# CoreBase-V2_0.net
KiCad netlist of a schematic drawn in Altium Designer
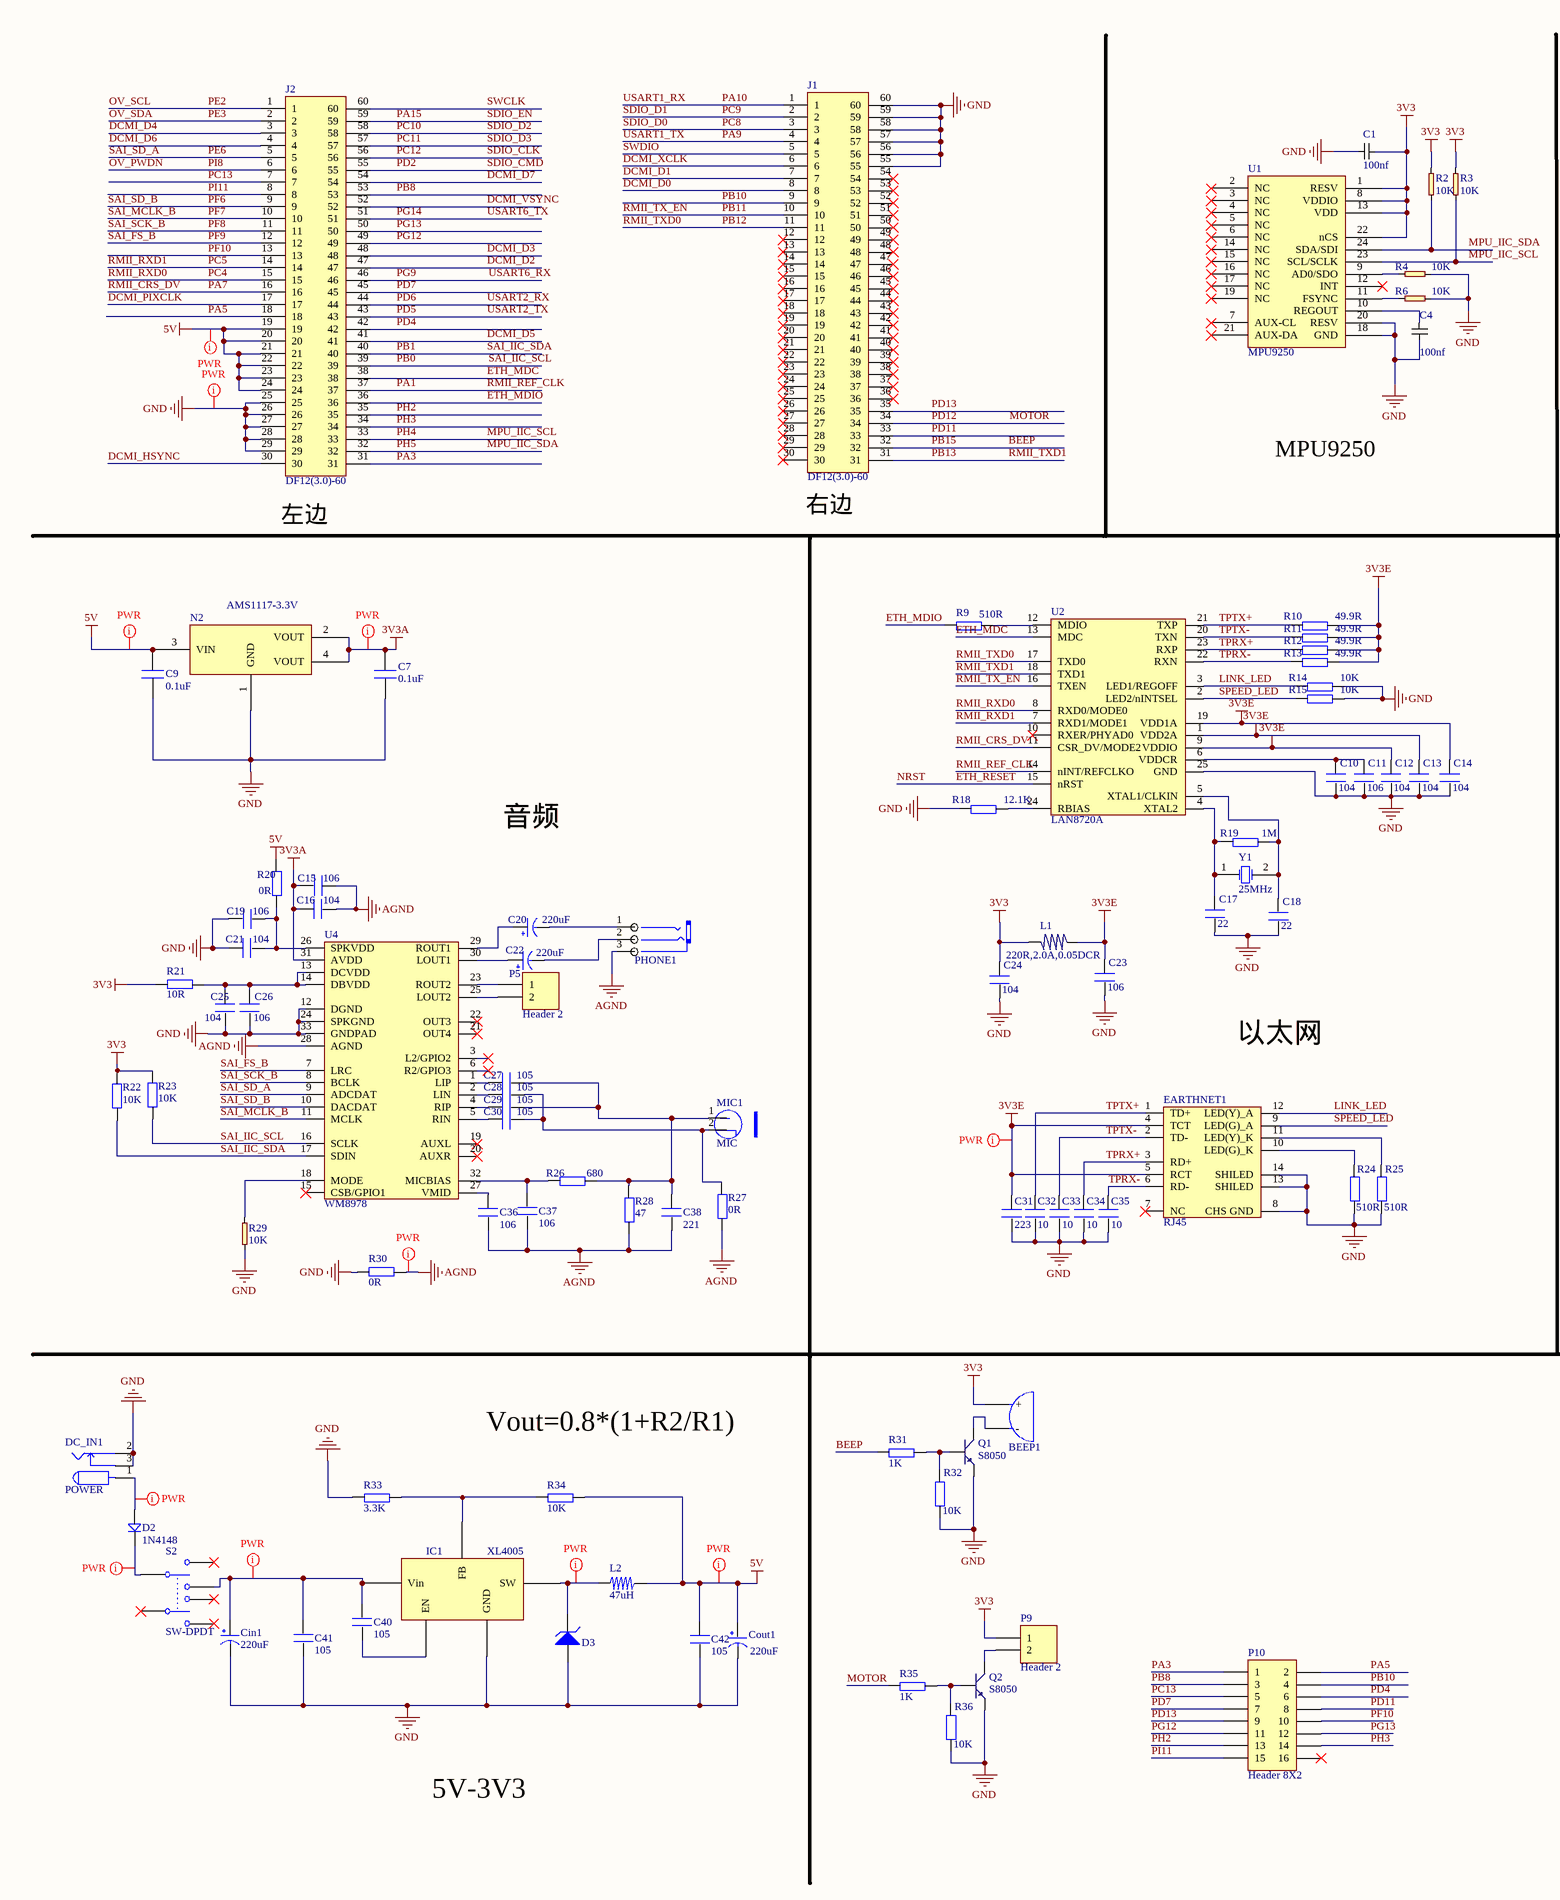
[diagram p0: CoreBase-V2.0.SchDoc, left]
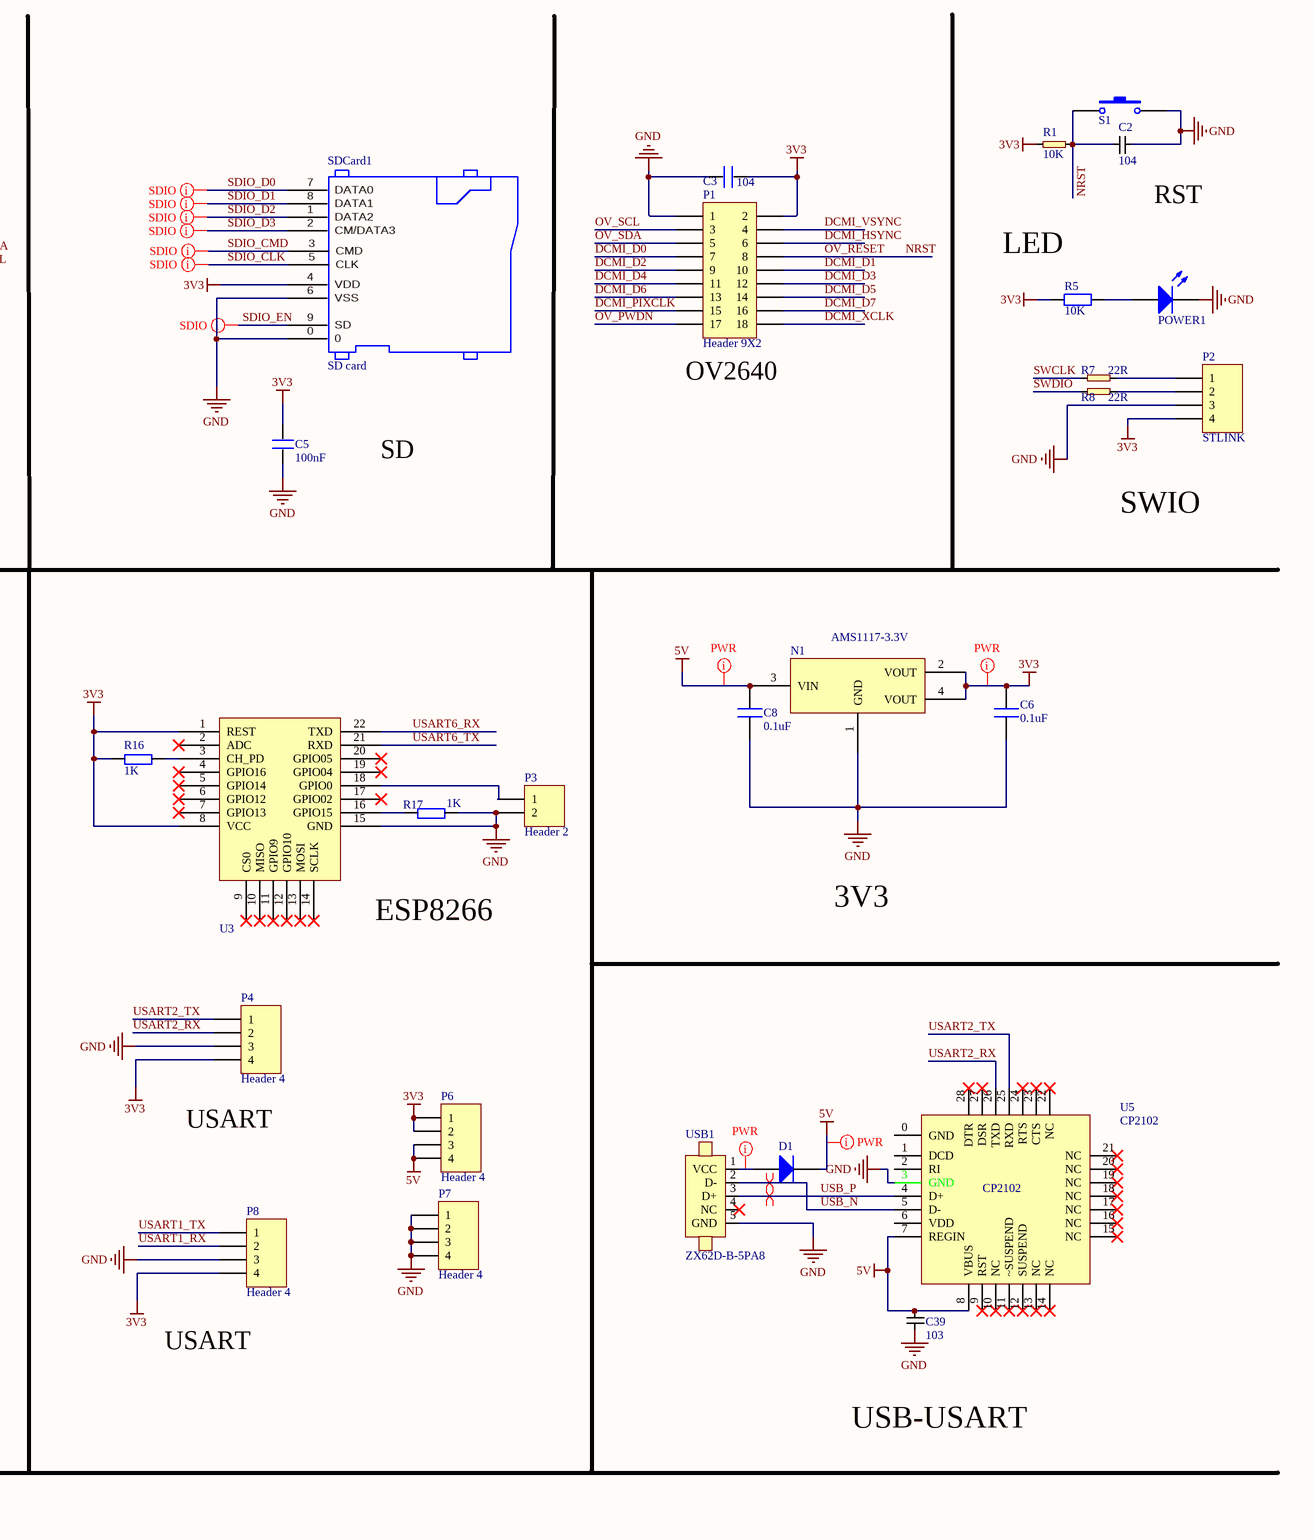
[diagram p1: CoreBase-V2.0.SchDoc, right]

(export (version "E")
  (design (tool "Eeschema 10.0.6"))
  (components
    (comp (ref "BEEP1") (value "BEEP") (footprint "SOT12-7.6") (libsource (lib "newcar") (part "BEEP")))
    (comp (ref "C1") (value "100nf") (footprint "0603_C") (libsource (lib "STM32") (part "C")))
    (comp (ref "C2") (value "104") (footprint "0603_C") (libsource (lib "我的原件") (part "C")))
    (comp (ref "C3") (value "104") (footprint "0603_C") (libsource (lib "阿波罗STM32F4&F7底板封装库") (part "C")))
    (comp (ref "C4") (value "100nf") (footprint "0603_C") (libsource (lib "STM32") (part "C")))
    (comp (ref "C5") (value "100nF") (footprint "0603_C") (libsource (lib "阿波罗STM32F4&F7底板封装库") (part "C")))
    (comp (ref "C6")
      (value "0.1uF")
      (footprint "0603_C")
      (description "Capacitor")
      (libsource (lib "Liuzhx") (part "普通贴片电容"))
    )
    (comp (ref "C7")
      (value "0.1uF")
      (footprint "0603_C")
      (description "Capacitor")
      (libsource (lib "Liuzhx") (part "普通贴片电容"))
    )
    (comp (ref "C8")
      (value "0.1uF")
      (footprint "0603_C")
      (description "Capacitor")
      (libsource (lib "Liuzhx") (part "普通贴片电容"))
    )
    (comp (ref "C9")
      (value "0.1uF")
      (footprint "0603_C")
      (description "Capacitor")
      (libsource (lib "Liuzhx") (part "普通贴片电容"))
    )
    (comp (ref "C10") (value "104") (footprint "0603_C") (libsource (lib "阿波罗STM32F4&F7底板封装库") (part "C")))
    (comp (ref "C11") (value "106") (footprint "0603_C") (libsource (lib "阿波罗STM32F4&F7底板封装库") (part "C")))
    (comp (ref "C12") (value "104") (footprint "0603_C") (libsource (lib "阿波罗STM32F4&F7底板封装库") (part "C")))
    (comp (ref "C13") (value "104") (footprint "0603_C") (libsource (lib "阿波罗STM32F4&F7底板封装库") (part "C")))
    (comp (ref "C14") (value "104") (footprint "0603_C") (libsource (lib "阿波罗STM32F4&F7底板封装库") (part "C")))
    (comp (ref "C15") (value "106") (footprint "0603_C") (libsource (lib "阿波罗STM32F4&F7底板封装库") (part "C")))
    (comp (ref "C16") (value "104") (footprint "0603_C") (libsource (lib "阿波罗STM32F4&F7底板封装库") (part "C")))
    (comp (ref "C17") (value "22") (footprint "0603_C") (libsource (lib "阿波罗STM32F4&F7底板封装库") (part "C")))
    (comp (ref "C18") (value "22") (footprint "0603_C") (libsource (lib "阿波罗STM32F4&F7底板封装库") (part "C")))
    (comp (ref "C19") (value "106") (footprint "0603_C") (libsource (lib "阿波罗STM32F4&F7底板封装库") (part "C")))
    (comp (ref "C20")
      (value "220uF")
      (footprint "CC6.56.5")
      (libsource (lib "阿波罗STM32F4&F7底板封装库") (part "CAP"))
    )
    (comp (ref "C21") (value "104") (footprint "0603_C") (libsource (lib "阿波罗STM32F4&F7底板封装库") (part "C")))
    (comp (ref "C22")
      (value "220uF")
      (footprint "CC6.56.5")
      (libsource (lib "阿波罗STM32F4&F7底板封装库") (part "CAP"))
    )
    (comp (ref "C23") (value "106") (footprint "0603_C") (libsource (lib "阿波罗STM32F4&F7底板封装库") (part "C")))
    (comp (ref "C24") (value "104") (footprint "0603_C") (libsource (lib "阿波罗STM32F4&F7底板封装库") (part "C")))
    (comp (ref "C25") (value "104") (footprint "0603_C") (libsource (lib "阿波罗STM32F4&F7底板封装库") (part "C")))
    (comp (ref "C26") (value "106") (footprint "0603_C") (libsource (lib "阿波罗STM32F4&F7底板封装库") (part "C")))
    (comp (ref "C27") (value "105") (footprint "0603_C") (libsource (lib "阿波罗STM32F4&F7底板封装库") (part "C")))
    (comp (ref "C28") (value "105") (footprint "0603_C") (libsource (lib "阿波罗STM32F4&F7底板封装库") (part "C")))
    (comp (ref "C29") (value "105") (footprint "0603_C") (libsource (lib "阿波罗STM32F4&F7底板封装库") (part "C")))
    (comp (ref "C30") (value "105") (footprint "0603_C") (libsource (lib "阿波罗STM32F4&F7底板封装库") (part "C")))
    (comp (ref "C31") (value "223") (footprint "0603_C") (libsource (lib "阿波罗STM32F4&F7底板封装库") (part "C")))
    (comp (ref "C32") (value "10") (footprint "0603_C") (libsource (lib "阿波罗STM32F4&F7底板封装库") (part "C")))
    (comp (ref "C33") (value "10") (footprint "0603_C") (libsource (lib "阿波罗STM32F4&F7底板封装库") (part "C")))
    (comp (ref "C34") (value "10") (footprint "0603_C") (libsource (lib "阿波罗STM32F4&F7底板封装库") (part "C")))
    (comp (ref "C35") (value "10") (footprint "0603_C") (libsource (lib "阿波罗STM32F4&F7底板封装库") (part "C")))
    (comp (ref "C36") (value "106") (footprint "0603_C") (libsource (lib "阿波罗STM32F4&F7底板封装库") (part "C")))
    (comp (ref "C37") (value "106") (footprint "0603_C") (libsource (lib "阿波罗STM32F4&F7底板封装库") (part "C")))
    (comp (ref "C38") (value "221") (footprint "0603_C") (libsource (lib "阿波罗STM32F4&F7底板封装库") (part "C")))
    (comp (ref "C39") (value "103") (footprint "0603_C") (libsource (lib "我的原件") (part "C")))
    (comp (ref "C40") (value "105") (footprint "0603_C") (libsource (lib "WARSHIP") (part "C")))
    (comp (ref "C41") (value "105") (footprint "0603_C") (libsource (lib "WARSHIP") (part "C")))
    (comp (ref "C42") (value "105") (footprint "0603_C") (libsource (lib "WARSHIP") (part "C")))
    (comp (ref "Cin1") (value "220uF") (footprint "CC6.56.5") (libsource (lib "WARSHIP") (part "CAP")))
    (comp (ref "Cout1") (value "220uF") (footprint "CC6.56.5") (libsource (lib "WARSHIP") (part "CAP")))
    (comp (ref "D1") (value "1N5819") (footprint "SOD-123") (libsource (lib "我的原件") (part "D")))
    (comp (ref "D2") (value "1N4148") (footprint "SOD-123") (libsource (lib "阿波罗STM32F4&F7底板封装库") (part "D")))
    (comp (ref "D3")
      (value "Diode  Zener")
      (footprint "SMA(DO-214AC)")
      (description "Zener Diode")
      (fields (field (name "PUBLISHER") "Altium Limited"))
      (libsource (lib "3D_library") (part "Diode  Zener"))
    )
    (comp (ref "DC_IN1")
      (value "POWER")
      (footprint "DC10B")
      (libsource (lib "阿波罗STM32F4&F7底板封装库") (part "POW"))
    )
    (comp (ref "EARTHNET1")
      (value "RJ45")
      (footprint "HR911105A")
      (libsource (lib "阿波罗STM32F4&F7底板封装库") (part "HR911105"))
    )
    (comp (ref "IC1") (value "XL4005") (footprint "TO-263-5") (libsource (lib "CMYKLEO") (part "XL4005")))
    (comp (ref "J1")
      (value "DF12(3.0)-60")
      (footprint "DF12(3.0)-60DS-Top")
      (libsource (lib "我的原件") (part "DF12(3.0)-60"))
    )
    (comp (ref "J2")
      (value "DF12(3.0)-60")
      (footprint "DF12(3.0)-60DS-TOP")
      (libsource (lib "我的原件") (part "DF12(3.0)-60"))
    )
    (comp (ref "L1")
      (value "220R,2.0A,0.05DCR")
      (footprint "0603P")
      (libsource (lib "阿波罗STM32F4&F7底板封装库") (part "L"))
    )
    (comp (ref "L2")
      (value "47uH")
      (footprint "L_SOP74")
      (libsource (lib "阿波罗STM32F4&F7底板封装库") (part "L_SOP"))
    )
    (comp (ref "MIC1")
      (value "MIC")
      (footprint "MIC-6022")
      (libsource (lib "阿波罗STM32F4&F7底板封装库") (part "MIC"))
    )
    (comp (ref "N1")
      (value "AMS1117-3.3V")
      (footprint "SOT223")
      (libsource (lib "Liuzhx") (part "AMS1117-3.3V"))
    )
    (comp (ref "N2")
      (value "AMS1117-3.3V")
      (footprint "SOT223")
      (libsource (lib "Liuzhx") (part "AMS1117-3.3V"))
    )
    (comp (ref "P1")
      (value "Header 9X2")
      (footprint "HDR2X9")
      (description "Header, 9-Pin, Dual row")
      (fields (field (name "PUBLISHER") "Altium Limited"))
      (libsource (lib "Miscellaneous Connectors") (part "Header 9X2"))
    )
    (comp (ref "P2")
      (value "STLINK")
      (footprint "HDR1X4")
      (description "Header, 4-Pin")
      (fields (field (name "PUBLISHER") "Altium Limited"))
      (libsource (lib "Miscellaneous Connectors") (part "Header 4"))
    )
    (comp (ref "P3")
      (value "Header 2")
      (footprint "HDR1X2")
      (description "Header, 2-Pin")
      (fields (field (name "PUBLISHER") "Altium Limited"))
      (libsource (lib "Miscellaneous Connectors") (part "Header 2"))
    )
    (comp (ref "P4")
      (value "Header 4")
      (footprint "HDR1X4")
      (description "Header, 4-Pin")
      (fields (field (name "PUBLISHER") "Altium Limited"))
      (libsource (lib "Miscellaneous Connectors") (part "Header 4"))
    )
    (comp (ref "P5")
      (value "Header 2")
      (footprint "HDR1X2")
      (description "Header, 2-Pin")
      (fields (field (name "PUBLISHER") "Altium Limited"))
      (libsource (lib "Miscellaneous Connectors") (part "Header 2"))
    )
    (comp (ref "P6")
      (value "Header 4")
      (footprint "HDR1X4")
      (description "Header, 4-Pin")
      (fields (field (name "PUBLISHER") "Altium Limited"))
      (libsource (lib "Miscellaneous Connectors") (part "Header 4"))
    )
    (comp (ref "P7")
      (value "Header 4")
      (footprint "HDR1X4")
      (description "Header, 4-Pin")
      (fields (field (name "PUBLISHER") "Altium Limited"))
      (libsource (lib "Miscellaneous Connectors") (part "Header 4"))
    )
    (comp (ref "P8")
      (value "Header 4")
      (footprint "HDR1X4")
      (description "Header, 4-Pin")
      (fields (field (name "PUBLISHER") "Altium Limited"))
      (libsource (lib "Miscellaneous Connectors") (part "Header 4"))
    )
    (comp (ref "P9")
      (value "Header 2")
      (footprint "HDR1X2")
      (description "Header, 2-Pin")
      (fields (field (name "PUBLISHER") "Altium Limited"))
      (libsource (lib "Miscellaneous Connectors") (part "Header 2"))
    )
    (comp (ref "P10")
      (value "Header 8X2")
      (footprint "HDR2X8")
      (description "Header, 8-Pin, Dual row")
      (fields (field (name "PUBLISHER") "Altium Limited"))
      (libsource (lib "Miscellaneous Connectors") (part "Header 8X2"))
    )
    (comp (ref "PHONE1")
      (value "PHONE")
      (footprint "PHONE_ST")
      (libsource (lib "阿波罗STM32F4&F7底板封装库") (part "PHONE_M"))
    )
    (comp (ref "POWER1") (value "LED") (footprint "0603P") (libsource (lib "元件库") (part "LED")))
    (comp (ref "Q1")
      (value "S8050")
      (footprint "SOT-23R")
      (description "8050/BCW846/BCW847")
      (libsource (lib "阿波罗STM32F4&F7底板封装库") (part "NPN"))
    )
    (comp (ref "Q2")
      (value "S8050")
      (footprint "SOT-23R")
      (description "8050/BCW846/BCW847")
      (libsource (lib "阿波罗STM32F4&F7底板封装库") (part "NPN"))
    )
    (comp (ref "R1") (value "10K") (footprint "0603_R") (libsource (lib "我的原件") (part "R")))
    (comp (ref "R2") (value "10K") (footprint "0603_R") (libsource (lib "STM32") (part "R")))
    (comp (ref "R3") (value "10K") (footprint "0603_R") (libsource (lib "STM32") (part "R")))
    (comp (ref "R4") (value "10K") (footprint "0603_R") (libsource (lib "") (part "R_1")))
    (comp (ref "R5") (value "10K") (footprint "0603_R") (libsource (lib "元件库") (part "Res")))
    (comp (ref "R6") (value "10K") (footprint "0603_R") (libsource (lib "") (part "R_1")))
    (comp (ref "R7") (value "22R") (footprint "0603_R") (libsource (lib "") (part "R_2")))
    (comp (ref "R8") (value "22R") (footprint "0603_R") (libsource (lib "") (part "R_2")))
    (comp (ref "R9") (value "510R") (footprint "0603_R") (libsource (lib "阿波罗STM32F4&F7底板封装库") (part "R")))
    (comp (ref "R10") (value "49.9R") (footprint "0603_R") (libsource (lib "阿波罗STM32F4&F7底板封装库") (part "R")))
    (comp (ref "R11") (value "49.9R") (footprint "0603_R") (libsource (lib "阿波罗STM32F4&F7底板封装库") (part "R")))
    (comp (ref "R12") (value "49.9R") (footprint "0603_R") (libsource (lib "阿波罗STM32F4&F7底板封装库") (part "R")))
    (comp (ref "R13") (value "49.9R") (footprint "0603_R") (libsource (lib "阿波罗STM32F4&F7底板封装库") (part "R")))
    (comp (ref "R14") (value "10K") (footprint "0603_R") (libsource (lib "阿波罗STM32F4&F7底板封装库") (part "R")))
    (comp (ref "R15") (value "10K") (footprint "0603_R") (libsource (lib "阿波罗STM32F4&F7底板封装库") (part "R")))
    (comp (ref "R16") (value "1K") (footprint "0603_R") (libsource (lib "阿波罗STM32F4&F7底板封装库") (part "R")))
    (comp (ref "R17") (value "1K") (footprint "0603_R") (libsource (lib "阿波罗STM32F4&F7底板封装库") (part "R")))
    (comp (ref "R18") (value "12.1K") (footprint "0603_R") (libsource (lib "阿波罗STM32F4&F7底板封装库") (part "R")))
    (comp (ref "R19") (value "1M") (footprint "0603_R") (libsource (lib "阿波罗STM32F4&F7底板封装库") (part "R")))
    (comp (ref "R20") (value "0R") (footprint "0603_R") (libsource (lib "阿波罗STM32F4&F7底板封装库") (part "R")))
    (comp (ref "R21") (value "10R") (footprint "0603_R") (libsource (lib "阿波罗STM32F4&F7底板封装库") (part "R")))
    (comp (ref "R22") (value "10K") (footprint "0603_R") (libsource (lib "阿波罗STM32F4&F7底板封装库") (part "R")))
    (comp (ref "R23") (value "10K") (footprint "0603_R") (libsource (lib "阿波罗STM32F4&F7底板封装库") (part "R")))
    (comp (ref "R24") (value "510R") (footprint "0603_R") (libsource (lib "阿波罗STM32F4&F7底板封装库") (part "R")))
    (comp (ref "R25") (value "510R") (footprint "0603_R") (libsource (lib "阿波罗STM32F4&F7底板封装库") (part "R")))
    (comp (ref "R26") (value "680") (footprint "0603_R") (libsource (lib "阿波罗STM32F4&F7底板封装库") (part "R")))
    (comp (ref "R27") (value "0R") (footprint "0603_R") (libsource (lib "阿波罗STM32F4&F7底板封装库") (part "R")))
    (comp (ref "R28") (value "47") (footprint "0603_R") (libsource (lib "阿波罗STM32F4&F7底板封装库") (part "R")))
    (comp (ref "R29") (value "10K") (footprint "0603_R") (libsource (lib "CoreF429") (part "R")))
    (comp (ref "R30") (value "0R") (footprint "0603_R") (libsource (lib "阿波罗STM32F4&F7底板封装库") (part "R")))
    (comp (ref "R31") (value "1K") (footprint "0603_R") (libsource (lib "阿波罗STM32F4&F7底板封装库") (part "R")))
    (comp (ref "R32") (value "10K") (footprint "0603_R") (libsource (lib "阿波罗STM32F4&F7底板封装库") (part "R")))
    (comp (ref "R33") (value "3.3K") (footprint "0603_R") (libsource (lib "WARSHIP") (part "R")))
    (comp (ref "R34") (value "10K") (footprint "0603_R") (libsource (lib "WARSHIP") (part "R")))
    (comp (ref "R35") (value "1K") (footprint "0603_R") (libsource (lib "阿波罗STM32F4&F7底板封装库") (part "R")))
    (comp (ref "R36") (value "10K") (footprint "0603_R") (libsource (lib "阿波罗STM32F4&F7底板封装库") (part "R")))
    (comp (ref "S1") (value "SW-PB") (footprint "SW-3625") (libsource (lib "我的原理图库") (part "SW-PB")))
    (comp (ref "S2")
      (value "SW-DPDT")
      (footprint "SW-DPDT")
      (description "Double-Pole, Double-Throw Switch")
      (fields (field (name "PUBLISHER") "Altium Limited"))
      (libsource (lib "我的原理图库") (part "SW-DPDT"))
    )
    (comp (ref "SDCard1") (value "SD card") (footprint "SD_CARD") (libsource (lib "元件库") (part "SD card")))
    (comp (ref "U1") (value "MPU9250") (footprint "QFN24") (libsource (lib "Wunter") (part "MPU9250")))
    (comp (ref "U2")
      (value "LAN8720A")
      (footprint "QFN24")
      (description "ETH PHY")
      (libsource (lib "阿波罗STM32F4&F7底板封装库") (part "LAN8720"))
    )
    (comp (ref "U3") (value "ESP8266") (footprint "ESP-8266") (libsource (lib "Wunter") (part "ESP8266")))
    (comp (ref "U4")
      (value "WM8978")
      (footprint "WM8978")
      (description "24bit ADC&DAC")
      (libsource (lib "阿波罗STM32F4&F7底板封装库") (part "WM8978"))
    )
    (comp (ref "U5") (value "CP2102") (footprint "QFN-28") (libsource (lib "我的原件") (part "CP2102")))
    (comp (ref "USB1")
      (value "ZX62D-B-5PA8")
      (footprint "Micro_USB")
      (libsource (lib "我的原件") (part "micro usb"))
    )
    (comp (ref "Y1")
      (value "25MHz")
      (footprint "XTAL_US")
      (description "Crystal Oscillator")
      (fields (field (name "PUBLISHER") "Altium Limited"))
      (libsource (lib "阿波罗STM32F4&F7底板封装库") (part "XTAL"))
    )
  )
  (nets
    (net (code "1") (name "/BEEP") (class "Default")
      (node (ref "J1") (pin "32") (pinfunction "32_32") (pintype "passive"))
      (node (ref "R31") (pin "1") (pintype "passive"))
    )
    (net (code "2") (name "/DCMI_D0") (class "Default")
      (node (ref "J1") (pin "8") (pinfunction "8_8") (pintype "passive"))
      (node (ref "P1") (pin "7") (pinfunction "7_7") (pintype "passive"))
    )
    (net (code "3") (name "/DCMI_D1") (class "Default")
      (node (ref "J1") (pin "7") (pinfunction "7_7") (pintype "passive"))
      (node (ref "P1") (pin "10") (pinfunction "10_10") (pintype "passive"))
    )
    (net (code "4") (name "/DCMI_D2") (class "Default")
      (node (ref "J2") (pin "47") (pinfunction "47_47") (pintype "passive"))
      (node (ref "P1") (pin "9") (pinfunction "9_9") (pintype "passive"))
    )
    (net (code "5") (name "/DCMI_D3") (class "Default")
      (node (ref "J2") (pin "48") (pinfunction "48_48") (pintype "passive"))
      (node (ref "P1") (pin "12") (pinfunction "12_12") (pintype "passive"))
    )
    (net (code "6") (name "/DCMI_D4") (class "Default")
      (node (ref "J2") (pin "3") (pinfunction "3_3") (pintype "passive"))
      (node (ref "P1") (pin "11") (pinfunction "11_11") (pintype "passive"))
    )
    (net (code "7") (name "/DCMI_D5") (class "Default")
      (node (ref "J2") (pin "41") (pinfunction "41_41") (pintype "passive"))
      (node (ref "P1") (pin "14") (pinfunction "14_14") (pintype "passive"))
    )
    (net (code "8") (name "/DCMI_D6") (class "Default")
      (node (ref "J2") (pin "4") (pinfunction "4_4") (pintype "passive"))
      (node (ref "P1") (pin "13") (pinfunction "13_13") (pintype "passive"))
    )
    (net (code "9") (name "/DCMI_D7") (class "Default")
      (node (ref "J2") (pin "54") (pinfunction "54_54") (pintype "passive"))
      (node (ref "P1") (pin "16") (pinfunction "16_16") (pintype "passive"))
    )
    (net (code "10") (name "/DCMI_HSYNC") (class "Default")
      (node (ref "J2") (pin "30") (pinfunction "30_30") (pintype "passive"))
      (node (ref "P1") (pin "6") (pinfunction "6_6") (pintype "passive"))
    )
    (net (code "11") (name "/DCMI_PIXCLK") (class "Default")
      (node (ref "J2") (pin "17") (pinfunction "17_17") (pintype "passive"))
      (node (ref "P1") (pin "15") (pinfunction "15_15") (pintype "passive"))
    )
    (net (code "12") (name "/DCMI_VSYNC") (class "Default")
      (node (ref "J2") (pin "52") (pinfunction "52_52") (pintype "passive"))
      (node (ref "P1") (pin "4") (pinfunction "4_4") (pintype "passive"))
    )
    (net (code "13") (name "/DCMI_XCLK") (class "Default")
      (node (ref "J1") (pin "6") (pinfunction "6_6") (pintype "passive"))
      (node (ref "P1") (pin "18") (pinfunction "18_18") (pintype "passive"))
    )
    (net (code "14") (name "/ETH_MDC") (class "Default")
      (node (ref "J2") (pin "38") (pinfunction "38_38") (pintype "passive"))
      (node (ref "U2") (pin "13") (pinfunction "MDC_13") (pintype "passive"))
    )
    (net (code "15") (name "/ETH_MDIO") (class "Default")
      (node (ref "J2") (pin "36") (pinfunction "36_36") (pintype "passive"))
      (node (ref "R9") (pin "1") (pintype "passive"))
    )
    (net (code "16") (name "/ETH_RESET") (class "Default")
      (node (ref "C2") (pin "1") (pinfunction "1_1") (pintype "passive"))
      (node (ref "P1") (pin "8") (pinfunction "8_8") (pintype "passive"))
      (node (ref "R1") (pin "2") (pintype "passive"))
      (node (ref "S1") (pin "1") (pinfunction "1_1") (pintype "passive"))
      (node (ref "U2") (pin "15") (pinfunction "nRST_15") (pintype "passive"))
    )
    (net (code "17") (name "/LINK_LED") (class "Default")
      (node (ref "EARTHNET1") (pin "12") (pinfunction "LED(Y)_A_12") (pintype "passive"))
      (node (ref "R14") (pin "1") (pintype "passive"))
      (node (ref "U2") (pin "3") (pinfunction "LED1/REGOFF_3") (pintype "passive"))
    )
    (net (code "18") (name "/MOTOR") (class "Default")
      (node (ref "J1") (pin "34") (pinfunction "34_34") (pintype "passive"))
      (node (ref "R35") (pin "1") (pintype "passive"))
    )
    (net (code "19") (name "/MPU_IIC_SCL") (class "Default")
      (node (ref "J2") (pin "33") (pinfunction "33_33") (pintype "passive"))
      (node (ref "R3") (pin "1") (pintype "passive"))
      (node (ref "U1") (pin "23") (pinfunction "SCL/SCLK_23") (pintype "passive"))
    )
    (net (code "20") (name "/MPU_IIC_SDA") (class "Default")
      (node (ref "J2") (pin "32") (pinfunction "32_32") (pintype "passive"))
      (node (ref "R2") (pin "1") (pintype "passive"))
      (node (ref "U1") (pin "24") (pinfunction "SDA/SDI_24") (pintype "passive"))
    )
    (net (code "21") (name "/OV_PWDN") (class "Default")
      (node (ref "J2") (pin "6") (pinfunction "6_6") (pintype "passive"))
      (node (ref "P1") (pin "17") (pinfunction "17_17") (pintype "passive"))
    )
    (net (code "22") (name "/OV_SCL") (class "Default")
      (node (ref "J2") (pin "1") (pinfunction "1_1") (pintype "passive"))
      (node (ref "P1") (pin "3") (pinfunction "3_3") (pintype "passive"))
    )
    (net (code "23") (name "/OV_SDA") (class "Default")
      (node (ref "J2") (pin "2") (pinfunction "2_2") (pintype "passive"))
      (node (ref "P1") (pin "5") (pinfunction "5_5") (pintype "passive"))
    )
    (net (code "24") (name "/PA1") (class "Default")
      (node (ref "J2") (pin "37") (pinfunction "37_37") (pintype "passive"))
      (node (ref "U2") (pin "14") (pinfunction "nINT/REFCLKO_14") (pintype "passive"))
    )
    (net (code "25") (name "/PA3") (class "Default")
      (node (ref "J2") (pin "31") (pinfunction "31_31") (pintype "passive"))
      (node (ref "P10") (pin "1") (pinfunction "1_1") (pintype "passive"))
    )
    (net (code "26") (name "/PA5") (class "Default")
      (node (ref "J2") (pin "18") (pinfunction "18_18") (pintype "passive"))
      (node (ref "P10") (pin "2") (pinfunction "2_2") (pintype "passive"))
    )
    (net (code "27") (name "/PA7") (class "Default")
      (node (ref "J2") (pin "16") (pinfunction "16_16") (pintype "passive"))
      (node (ref "U2") (pin "11") (pinfunction "CSR_DV/MODE2_11") (pintype "passive"))
    )
    (net (code "28") (name "/PA9") (class "Default")
      (node (ref "J1") (pin "4") (pinfunction "4_4") (pintype "passive"))
      (node (ref "P8") (pin "1") (pinfunction "1_1") (pintype "passive"))
    )
    (net (code "29") (name "/PA10") (class "Default")
      (node (ref "J1") (pin "1") (pinfunction "1_1") (pintype "passive"))
      (node (ref "P8") (pin "2") (pinfunction "2_2") (pintype "passive"))
    )
    (net (code "30") (name "/PA15") (class "Default")
      (node (ref "J2") (pin "59") (pinfunction "59_59") (pintype "passive"))
      (node (ref "SDCard1") (pin "9") (pinfunction "SD_9") (pintype "passive"))
    )
    (net (code "31") (name "/PB0") (class "Default")
      (node (ref "J2") (pin "39") (pinfunction "39_39") (pintype "passive"))
      (node (ref "R23") (pin "2") (pintype "passive"))
      (node (ref "U4") (pin "16") (pinfunction "SCLK_16") (pintype "passive"))
    )
    (net (code "32") (name "/PB1") (class "Default")
      (node (ref "J2") (pin "40") (pinfunction "40_40") (pintype "passive"))
      (node (ref "R22") (pin "2") (pintype "passive"))
      (node (ref "U4") (pin "17") (pinfunction "SDIN_17") (pintype "passive"))
    )
    (net (code "33") (name "/PB8") (class "Default")
      (node (ref "J2") (pin "53") (pinfunction "53_53") (pintype "passive"))
      (node (ref "P10") (pin "3") (pinfunction "3_3") (pintype "passive"))
    )
    (net (code "34") (name "/PB10") (class "Default")
      (node (ref "J1") (pin "9") (pinfunction "9_9") (pintype "passive"))
      (node (ref "P10") (pin "4") (pinfunction "4_4") (pintype "passive"))
    )
    (net (code "35") (name "/PB11") (class "Default")
      (node (ref "J1") (pin "10") (pinfunction "10_10") (pintype "passive"))
      (node (ref "U2") (pin "16") (pinfunction "TXEN_16") (pintype "passive"))
    )
    (net (code "36") (name "/PB12") (class "Default")
      (node (ref "J1") (pin "11") (pinfunction "11_11") (pintype "passive"))
      (node (ref "U2") (pin "17") (pinfunction "TXD0_17") (pintype "passive"))
    )
    (net (code "37") (name "/PB13") (class "Default")
      (node (ref "J1") (pin "31") (pinfunction "31_31") (pintype "passive"))
      (node (ref "U2") (pin "18") (pinfunction "TXD1_18") (pintype "passive"))
    )
    (net (code "38") (name "/PC4") (class "Default")
      (node (ref "J2") (pin "15") (pinfunction "15_15") (pintype "passive"))
      (node (ref "U2") (pin "8") (pinfunction "RXD0/MODE0_8") (pintype "passive"))
    )
    (net (code "39") (name "/PC5") (class "Default")
      (node (ref "J2") (pin "14") (pinfunction "14_14") (pintype "passive"))
      (node (ref "U2") (pin "7") (pinfunction "RXD1/MODE1_7") (pintype "passive"))
    )
    (net (code "40") (name "/PC8") (class "Default")
      (node (ref "J1") (pin "3") (pinfunction "3_3") (pintype "passive"))
      (node (ref "SDCard1") (pin "7") (pinfunction "DATA0_7") (pintype "passive"))
    )
    (net (code "41") (name "/PC9") (class "Default")
      (node (ref "J1") (pin "2") (pinfunction "2_2") (pintype "passive"))
      (node (ref "SDCard1") (pin "8") (pinfunction "DATA1_8") (pintype "passive"))
    )
    (net (code "42") (name "/PC10") (class "Default")
      (node (ref "J2") (pin "58") (pinfunction "58_58") (pintype "passive"))
      (node (ref "SDCard1") (pin "1") (pinfunction "DATA2_1") (pintype "passive"))
    )
    (net (code "43") (name "/PC11") (class "Default")
      (node (ref "J2") (pin "57") (pinfunction "57_57") (pintype "passive"))
      (node (ref "SDCard1") (pin "2") (pinfunction "CM/DATA3_2") (pintype "passive"))
    )
    (net (code "44") (name "/PC12") (class "Default")
      (node (ref "J2") (pin "56") (pinfunction "56_56") (pintype "passive"))
      (node (ref "SDCard1") (pin "5") (pinfunction "CLK_5") (pintype "passive"))
    )
    (net (code "45") (name "/PC13") (class "Default")
      (node (ref "J2") (pin "7") (pinfunction "7_7") (pintype "passive"))
      (node (ref "P10") (pin "5") (pinfunction "5_5") (pintype "passive"))
    )
    (net (code "46") (name "/PD2") (class "Default")
      (node (ref "J2") (pin "55") (pinfunction "55_55") (pintype "passive"))
      (node (ref "SDCard1") (pin "3") (pinfunction "CMD_3") (pintype "passive"))
    )
    (net (code "47") (name "/PD4") (class "Default")
      (node (ref "J2") (pin "42") (pinfunction "42_42") (pintype "passive"))
      (node (ref "P10") (pin "6") (pinfunction "6_6") (pintype "passive"))
    )
    (net (code "48") (name "/PD5") (class "Default")
      (node (ref "J2") (pin "43") (pinfunction "43_43") (pintype "passive"))
      (node (ref "P4") (pin "1") (pinfunction "1_1") (pintype "passive"))
      (node (ref "U5") (pin "25") (pinfunction "RXD_25") (pintype "passive"))
    )
    (net (code "49") (name "/PD6") (class "Default")
      (node (ref "J2") (pin "44") (pinfunction "44_44") (pintype "passive"))
      (node (ref "P4") (pin "2") (pinfunction "2_2") (pintype "passive"))
      (node (ref "U5") (pin "26") (pinfunction "TXD_26") (pintype "passive"))
    )
    (net (code "50") (name "/PD7") (class "Default")
      (node (ref "J2") (pin "45") (pinfunction "45_45") (pintype "passive"))
      (node (ref "P10") (pin "7") (pinfunction "7_7") (pintype "passive"))
    )
    (net (code "51") (name "/PD11") (class "Default")
      (node (ref "J1") (pin "33") (pinfunction "33_33") (pintype "passive"))
      (node (ref "P10") (pin "8") (pinfunction "8_8") (pintype "passive"))
    )
    (net (code "52") (name "/PD13") (class "Default")
      (node (ref "J1") (pin "35") (pinfunction "35_35") (pintype "passive"))
      (node (ref "P10") (pin "9") (pinfunction "9_9") (pintype "passive"))
    )
    (net (code "53") (name "/PE6") (class "Default")
      (node (ref "J2") (pin "5") (pinfunction "5_5") (pintype "passive"))
      (node (ref "U4") (pin "9") (pinfunction "ADCDAT_9") (pintype "passive"))
    )
    (net (code "54") (name "/PF6") (class "Default")
      (node (ref "J2") (pin "9") (pinfunction "9_9") (pintype "passive"))
      (node (ref "U4") (pin "10") (pinfunction "DACDAT_10") (pintype "passive"))
    )
    (net (code "55") (name "/PF7") (class "Default")
      (node (ref "J2") (pin "10") (pinfunction "10_10") (pintype "passive"))
      (node (ref "U4") (pin "11") (pinfunction "MCLK_11") (pintype "passive"))
    )
    (net (code "56") (name "/PF8") (class "Default")
      (node (ref "J2") (pin "11") (pinfunction "11_11") (pintype "passive"))
      (node (ref "U4") (pin "8") (pinfunction "BCLK_8") (pintype "passive"))
    )
    (net (code "57") (name "/PF9") (class "Default")
      (node (ref "J2") (pin "12") (pinfunction "12_12") (pintype "passive"))
      (node (ref "U4") (pin "7") (pinfunction "LRC_7") (pintype "passive"))
    )
    (net (code "58") (name "/PF10") (class "Default")
      (node (ref "J2") (pin "13") (pinfunction "13_13") (pintype "passive"))
      (node (ref "P10") (pin "10") (pinfunction "10_10") (pintype "passive"))
    )
    (net (code "59") (name "/PG9") (class "Default")
      (node (ref "J2") (pin "46") (pinfunction "46_46") (pintype "passive"))
      (node (ref "U3") (pin "22") (pinfunction "TXD_22") (pintype "passive"))
    )
    (net (code "60") (name "/PG12") (class "Default")
      (node (ref "J2") (pin "49") (pinfunction "49_49") (pintype "passive"))
      (node (ref "P10") (pin "11") (pinfunction "11_11") (pintype "passive"))
    )
    (net (code "61") (name "/PG13") (class "Default")
      (node (ref "J2") (pin "50") (pinfunction "50_50") (pintype "passive"))
      (node (ref "P10") (pin "12") (pinfunction "12_12") (pintype "passive"))
    )
    (net (code "62") (name "/PG14") (class "Default")
      (node (ref "J2") (pin "51") (pinfunction "51_51") (pintype "passive"))
      (node (ref "U3") (pin "21") (pinfunction "RXD_21") (pintype "passive"))
    )
    (net (code "63") (name "/PH2") (class "Default")
      (node (ref "J2") (pin "35") (pinfunction "35_35") (pintype "passive"))
      (node (ref "P10") (pin "13") (pinfunction "13_13") (pintype "passive"))
    )
    (net (code "64") (name "/PH3") (class "Default")
      (node (ref "J2") (pin "34") (pinfunction "34_34") (pintype "passive"))
      (node (ref "P10") (pin "14") (pinfunction "14_14") (pintype "passive"))
    )
    (net (code "65") (name "/PI11") (class "Default")
      (node (ref "J2") (pin "8") (pinfunction "8_8") (pintype "passive"))
      (node (ref "P10") (pin "15") (pinfunction "15_15") (pintype "passive"))
    )
    (net (code "66") (name "/SPEED_LED") (class "Default")
      (node (ref "EARTHNET1") (pin "9") (pinfunction "LED(G)_A_9") (pintype "passive"))
      (node (ref "R15") (pin "1") (pintype "passive"))
      (node (ref "U2") (pin "2") (pinfunction "LED2/nINTSEL_2") (pintype "passive"))
    )
    (net (code "67") (name "/SWCLK") (class "Default")
      (node (ref "J2") (pin "60") (pinfunction "60_60") (pintype "passive"))
      (node (ref "R7") (pin "1") (pintype "passive"))
    )
    (net (code "68") (name "/SWDIO") (class "Default")
      (node (ref "J1") (pin "5") (pinfunction "5_5") (pintype "passive"))
      (node (ref "R8") (pin "1") (pintype "passive"))
    )
    (net (code "69") (name "/TPRX+") (class "Default")
      (node (ref "C34") (pin "2") (pintype "passive"))
      (node (ref "EARTHNET1") (pin "3") (pinfunction "RD+_3") (pintype "passive"))
      (node (ref "R12") (pin "1") (pintype "passive"))
      (node (ref "U2") (pin "23") (pinfunction "RXP_23") (pintype "passive"))
    )
    (net (code "70") (name "/TPRX-") (class "Default")
      (node (ref "C35") (pin "2") (pintype "passive"))
      (node (ref "EARTHNET1") (pin "6") (pinfunction "RD-_6") (pintype "passive"))
      (node (ref "R13") (pin "1") (pintype "passive"))
      (node (ref "U2") (pin "22") (pinfunction "RXN_22") (pintype "passive"))
    )
    (net (code "71") (name "/TPTX+") (class "Default")
      (node (ref "C32") (pin "2") (pintype "passive"))
      (node (ref "EARTHNET1") (pin "1") (pinfunction "TD+_1") (pintype "passive"))
      (node (ref "R10") (pin "1") (pintype "passive"))
      (node (ref "U2") (pin "21") (pinfunction "TXP_21") (pintype "passive"))
    )
    (net (code "72") (name "/TPTX-") (class "Default")
      (node (ref "C33") (pin "2") (pintype "passive"))
      (node (ref "EARTHNET1") (pin "2") (pinfunction "TD-_2") (pintype "passive"))
      (node (ref "R11") (pin "1") (pintype "passive"))
      (node (ref "U2") (pin "20") (pinfunction "TXN_20") (pintype "passive"))
    )
    (net (code "73") (name "/USB_N") (class "Default")
      (node (ref "U5") (pin "5") (pinfunction "D-_5") (pintype "passive"))
      (node (ref "USB1") (pin "2") (pinfunction "D-_2") (pintype "passive"))
    )
    (net (code "74") (name "/USB_P") (class "Default")
      (node (ref "U5") (pin "4") (pinfunction "D+_4") (pintype "passive"))
      (node (ref "USB1") (pin "3") (pinfunction "D+_3") (pintype "passive"))
    )
    (net (code "75") (name "3V3") (class "Default")
      (node (ref "BEEP1") (pin "1") (pinfunction "+_1") (pintype "passive"))
      (node (ref "C1") (pin "1") (pinfunction "1_1") (pintype "passive"))
      (node (ref "C24") (pin "2") (pintype "passive"))
      (node (ref "C3") (pin "2") (pintype "passive"))
      (node (ref "C5") (pin "2") (pintype "passive"))
      (node (ref "C6") (pin "1") (pinfunction "1_1") (pintype "passive"))
      (node (ref "L1") (pin "2") (pintype "passive"))
      (node (ref "N1") (pin "2") (pinfunction "VOUT_2") (pintype "passive"))
      (node (ref "N1") (pin "4") (pinfunction "VOUT_4") (pintype "passive"))
      (node (ref "P1") (pin "2") (pinfunction "2_2") (pintype "passive"))
      (node (ref "P2") (pin "4") (pinfunction "4_4") (pintype "passive"))
      (node (ref "P4") (pin "4") (pinfunction "4_4") (pintype "passive"))
      (node (ref "P6") (pin "1") (pinfunction "1_1") (pintype "passive"))
      (node (ref "P6") (pin "2") (pinfunction "2_2") (pintype "passive"))
      (node (ref "P8") (pin "4") (pinfunction "4_4") (pintype "passive"))
      (node (ref "P9") (pin "1") (pinfunction "1_1") (pintype "passive"))
      (node (ref "R1") (pin "1") (pintype "passive"))
      (node (ref "R16") (pin "1") (pintype "passive"))
      (node (ref "R2") (pin "2") (pintype "passive"))
      (node (ref "R21") (pin "2") (pintype "passive"))
      (node (ref "R22") (pin "1") (pintype "passive"))
      (node (ref "R23") (pin "1") (pintype "passive"))
      (node (ref "R3") (pin "2") (pintype "passive"))
      (node (ref "R5") (pin "1") (pinfunction "1_1") (pintype "passive"))
      (node (ref "SDCard1") (pin "4") (pinfunction "VDD_4") (pintype "passive"))
      (node (ref "U1") (pin "1") (pinfunction "RESV_1") (pintype "passive"))
      (node (ref "U1") (pin "13") (pinfunction "VDD_13") (pintype "passive"))
      (node (ref "U1") (pin "22") (pinfunction "nCS_22") (pintype "passive"))
      (node (ref "U1") (pin "8") (pinfunction "VDDIO_8") (pintype "passive"))
      (node (ref "U3") (pin "1") (pinfunction "REST_1") (pintype "passive"))
      (node (ref "U3") (pin "8") (pinfunction "VCC_8") (pintype "passive"))
    )
    (net (code "76") (name "3V3A") (class "Default")
      (node (ref "C15") (pin "2") (pintype "passive"))
      (node (ref "C16") (pin "1") (pintype "passive"))
      (node (ref "C7") (pin "1") (pinfunction "1_1") (pintype "passive"))
      (node (ref "N2") (pin "2") (pinfunction "VOUT_2") (pintype "passive"))
      (node (ref "N2") (pin "4") (pinfunction "VOUT_4") (pintype "passive"))
      (node (ref "U4") (pin "31") (pinfunction "AVDD_31") (pintype "passive"))
    )
    (net (code "77") (name "3V3E") (class "Default")
      (node (ref "C12") (pin "2") (pintype "passive"))
      (node (ref "C13") (pin "2") (pintype "passive"))
      (node (ref "C14") (pin "2") (pintype "passive"))
      (node (ref "C23") (pin "2") (pintype "passive"))
      (node (ref "C31") (pin "2") (pintype "passive"))
      (node (ref "EARTHNET1") (pin "4") (pinfunction "TCT_4") (pintype "passive"))
      (node (ref "EARTHNET1") (pin "5") (pinfunction "RCT_5") (pintype "passive"))
      (node (ref "L1") (pin "1") (pintype "passive"))
      (node (ref "R10") (pin "2") (pintype "passive"))
      (node (ref "R11") (pin "2") (pintype "passive"))
      (node (ref "R12") (pin "2") (pintype "passive"))
      (node (ref "R13") (pin "2") (pintype "passive"))
      (node (ref "U2") (pin "1") (pinfunction "VDD2A_1") (pintype "passive"))
      (node (ref "U2") (pin "19") (pinfunction "VDD1A_19") (pintype "passive"))
      (node (ref "U2") (pin "9") (pinfunction "VDDIO_9") (pintype "passive"))
    )
    (net (code "78") (name "5V") (class "Default")
      (node (ref "C39") (pin "2") (pinfunction "2_2") (pintype "passive"))
      (node (ref "C42") (pin "2") (pintype "passive"))
      (node (ref "C8") (pin "1") (pinfunction "1_1") (pintype "passive"))
      (node (ref "C9") (pin "1") (pinfunction "1_1") (pintype "passive"))
      (node (ref "Cout1") (pin "1") (pinfunction "VCC_1") (pintype "passive"))
      (node (ref "D1") (pin "2") (pinfunction "N_2") (pintype "passive"))
      (node (ref "J2") (pin "19") (pinfunction "19_19") (pintype "passive"))
      (node (ref "J2") (pin "20") (pinfunction "20_20") (pintype "passive"))
      (node (ref "J2") (pin "21") (pinfunction "21_21") (pintype "passive"))
      (node (ref "J2") (pin "22") (pinfunction "22_22") (pintype "passive"))
      (node (ref "J2") (pin "23") (pinfunction "23_23") (pintype "passive"))
      (node (ref "J2") (pin "24") (pinfunction "24_24") (pintype "passive"))
      (node (ref "L2") (pin "1") (pinfunction "1_1") (pintype "passive"))
      (node (ref "N1") (pin "3") (pinfunction "VIN_3") (pintype "passive"))
      (node (ref "N2") (pin "3") (pinfunction "VIN_3") (pintype "passive"))
      (node (ref "P6") (pin "3") (pinfunction "3_3") (pintype "passive"))
      (node (ref "P6") (pin "4") (pinfunction "4_4") (pintype "passive"))
      (node (ref "R20") (pin "2") (pintype "passive"))
      (node (ref "R34") (pin "2") (pintype "passive"))
      (node (ref "U5") (pin "7") (pinfunction "REGIN_7") (pintype "passive"))
      (node (ref "U5") (pin "8") (pinfunction "VBUS_8") (pintype "passive"))
    )
    (net (code "79") (name "AGND") (class "Default")
      (node (ref "C15") (pin "1") (pintype "passive"))
      (node (ref "C16") (pin "2") (pintype "passive"))
      (node (ref "C36") (pin "1") (pintype "passive"))
      (node (ref "C37") (pin "1") (pintype "passive"))
      (node (ref "C38") (pin "1") (pintype "passive"))
      (node (ref "PHONE1") (pin "3") (pinfunction "COM_3") (pintype "passive"))
      (node (ref "R27") (pin "1") (pintype "passive"))
      (node (ref "R28") (pin "1") (pintype "passive"))
      (node (ref "R30") (pin "1") (pintype "passive"))
      (node (ref "U4") (pin "28") (pinfunction "AGND_28") (pintype "passive"))
    )
    (net (code "80") (name "GND") (class "Default")
      (node (ref "C1") (pin "2") (pinfunction "2_2") (pintype "passive"))
      (node (ref "C10") (pin "1") (pintype "passive"))
      (node (ref "C11") (pin "1") (pintype "passive"))
      (node (ref "C12") (pin "1") (pintype "passive"))
      (node (ref "C13") (pin "1") (pintype "passive"))
      (node (ref "C14") (pin "1") (pintype "passive"))
      (node (ref "C17") (pin "1") (pintype "passive"))
      (node (ref "C18") (pin "1") (pintype "passive"))
      (node (ref "C19") (pin "2") (pintype "passive"))
      (node (ref "C2") (pin "2") (pinfunction "2_2") (pintype "passive"))
      (node (ref "C21") (pin "1") (pintype "passive"))
      (node (ref "C23") (pin "1") (pintype "passive"))
      (node (ref "C24") (pin "1") (pintype "passive"))
      (node (ref "C25") (pin "1") (pintype "passive"))
      (node (ref "C26") (pin "1") (pintype "passive"))
      (node (ref "C3") (pin "1") (pintype "passive"))
      (node (ref "C31") (pin "1") (pintype "passive"))
      (node (ref "C32") (pin "1") (pintype "passive"))
      (node (ref "C33") (pin "1") (pintype "passive"))
      (node (ref "C34") (pin "1") (pintype "passive"))
      (node (ref "C35") (pin "1") (pintype "passive"))
      (node (ref "C39") (pin "1") (pinfunction "1_1") (pintype "passive"))
      (node (ref "C4") (pin "1") (pinfunction "1_1") (pintype "passive"))
      (node (ref "C41") (pin "1") (pintype "passive"))
      (node (ref "C42") (pin "1") (pintype "passive"))
      (node (ref "C5") (pin "1") (pintype "passive"))
      (node (ref "C6") (pin "2") (pinfunction "2_2") (pintype "passive"))
      (node (ref "C7") (pin "2") (pinfunction "2_2") (pintype "passive"))
      (node (ref "C8") (pin "2") (pinfunction "2_2") (pintype "passive"))
      (node (ref "C9") (pin "2") (pinfunction "2_2") (pintype "passive"))
      (node (ref "Cin1") (pin "2") (pinfunction "GND_2") (pintype "passive"))
      (node (ref "Cout1") (pin "2") (pinfunction "GND_2") (pintype "passive"))
      (node (ref "D3") (pin "1") (pinfunction "A_1") (pintype "passive"))
      (node (ref "DC_IN1") (pin "2") (pintype "passive"))
      (node (ref "DC_IN1") (pin "3") (pintype "passive"))
      (node (ref "EARTHNET1") (pin "13") (pinfunction "SHILED_13") (pintype "passive"))
      (node (ref "EARTHNET1") (pin "14") (pinfunction "SHILED_14") (pintype "passive"))
      (node (ref "EARTHNET1") (pin "8") (pinfunction "CHS_GND_8") (pintype "passive"))
      (node (ref "IC1") (pin "1") (pinfunction "GND_1") (pintype "passive"))
      (node (ref "J1") (pin "55") (pinfunction "55_55") (pintype "passive"))
      (node (ref "J1") (pin "56") (pinfunction "56_56") (pintype "passive"))
      (node (ref "J1") (pin "57") (pinfunction "57_57") (pintype "passive"))
      (node (ref "J1") (pin "58") (pinfunction "58_58") (pintype "passive"))
      (node (ref "J1") (pin "59") (pinfunction "59_59") (pintype "passive"))
      (node (ref "J1") (pin "60") (pinfunction "60_60") (pintype "passive"))
      (node (ref "J2") (pin "25") (pinfunction "25_25") (pintype "passive"))
      (node (ref "J2") (pin "26") (pinfunction "26_26") (pintype "passive"))
      (node (ref "J2") (pin "27") (pinfunction "27_27") (pintype "passive"))
      (node (ref "J2") (pin "28") (pinfunction "28_28") (pintype "passive"))
      (node (ref "J2") (pin "29") (pinfunction "29_29") (pintype "passive"))
      (node (ref "N1") (pin "1") (pinfunction "GND_1") (pintype "passive"))
      (node (ref "N2") (pin "1") (pinfunction "GND_1") (pintype "passive"))
      (node (ref "P1") (pin "1") (pinfunction "1_1") (pintype "passive"))
      (node (ref "P2") (pin "3") (pinfunction "3_3") (pintype "passive"))
      (node (ref "P3") (pin "2") (pinfunction "2_2") (pintype "passive"))
      (node (ref "P4") (pin "3") (pinfunction "3_3") (pintype "passive"))
      (node (ref "P7") (pin "1") (pinfunction "1_1") (pintype "passive"))
      (node (ref "P7") (pin "2") (pinfunction "2_2") (pintype "passive"))
      (node (ref "P7") (pin "3") (pinfunction "3_3") (pintype "passive"))
      (node (ref "P7") (pin "4") (pinfunction "4_4") (pintype "passive"))
      (node (ref "P8") (pin "3") (pinfunction "3_3") (pintype "passive"))
      (node (ref "POWER1") (pin "2") (pinfunction "K_2") (pintype "passive"))
      (node (ref "Q1") (pin "1") (pinfunction "E_1") (pintype "passive"))
      (node (ref "Q2") (pin "1") (pinfunction "E_1") (pintype "passive"))
      (node (ref "R14") (pin "2") (pintype "passive"))
      (node (ref "R15") (pin "2") (pintype "passive"))
      (node (ref "R17") (pin "2") (pintype "passive"))
      (node (ref "R18") (pin "1") (pintype "passive"))
      (node (ref "R24") (pin "1") (pintype "passive"))
      (node (ref "R25") (pin "1") (pintype "passive"))
      (node (ref "R29") (pin "1") (pintype "passive"))
      (node (ref "R30") (pin "2") (pintype "passive"))
      (node (ref "R32") (pin "1") (pintype "passive"))
      (node (ref "R33") (pin "1") (pintype "passive"))
      (node (ref "R36") (pin "1") (pintype "passive"))
      (node (ref "R4") (pin "1") (pintype "passive"))
      (node (ref "R6") (pin "1") (pintype "passive"))
      (node (ref "S1") (pin "2") (pinfunction "2_2") (pintype "passive"))
      (node (ref "SDCard1") (pin "0") (pinfunction "0_0") (pintype "passive"))
      (node (ref "SDCard1") (pin "6") (pinfunction "VSS_6") (pintype "passive"))
      (node (ref "U1") (pin "18") (pinfunction "GND_18") (pintype "passive"))
      (node (ref "U1") (pin "20") (pinfunction "RESV_20") (pintype "passive"))
      (node (ref "U2") (pin "25") (pinfunction "GND_25") (pintype "passive"))
      (node (ref "U3") (pin "15") (pinfunction "GND_15") (pintype "passive"))
      (node (ref "U4") (pin "12") (pinfunction "DGND_12") (pintype "passive"))
      (node (ref "U4") (pin "24") (pinfunction "SPKGND_24") (pintype "passive"))
      (node (ref "U4") (pin "33") (pinfunction "GNDPAD_33") (pintype "passive"))
      (node (ref "U5") (pin "3") (pinfunction "GND_3") (pintype "passive"))
      (node (ref "USB1") (pin "5") (pinfunction "GND_5") (pintype "passive"))
    )
    (net (code "81") (name "Net-(BEEP1--)") (class "Default")
      (node (ref "BEEP1") (pin "2") (pinfunction "-_2") (pintype "passive"))
      (node (ref "Q1") (pin "3") (pinfunction "C_3") (pintype "passive"))
    )
    (net (code "82") (name "Net-(C20-GND)") (class "Default")
      (node (ref "C20") (pin "2") (pinfunction "GND_2") (pintype "passive"))
      (node (ref "PHONE1") (pin "1") (pinfunction "CHL_1") (pintype "passive"))
    )
    (net (code "83") (name "Net-(C20-VCC)") (class "Default")
      (node (ref "C20") (pin "1") (pinfunction "VCC_1") (pintype "passive"))
      (node (ref "U4") (pin "29") (pinfunction "ROUT1_29") (pintype "passive"))
    )
    (net (code "84") (name "Net-(C22-GND)") (class "Default")
      (node (ref "C22") (pin "2") (pinfunction "GND_2") (pintype "passive"))
      (node (ref "PHONE1") (pin "2") (pinfunction "CHR_2") (pintype "passive"))
    )
    (net (code "85") (name "Net-(C22-VCC)") (class "Default")
      (node (ref "C22") (pin "1") (pinfunction "VCC_1") (pintype "passive"))
      (node (ref "U4") (pin "30") (pinfunction "LOUT1_30") (pintype "passive"))
    )
    (net (code "86") (name "Net-(Cin1-VCC)") (class "Default")
      (node (ref "C40") (pin "2") (pintype "passive"))
      (node (ref "C41") (pin "2") (pintype "passive"))
      (node (ref "Cin1") (pin "1") (pinfunction "VCC_1") (pintype "passive"))
      (node (ref "IC1") (pin "5") (pinfunction "Vin_5") (pintype "passive"))
      (node (ref "S2") (pin "3") (pinfunction "3_3") (pintype "passive"))
    )
    (net (code "87") (name "Net-(D1-P)") (class "Default")
      (node (ref "D1") (pin "1") (pinfunction "P_1") (pintype "passive"))
      (node (ref "USB1") (pin "1") (pinfunction "VCC_1") (pintype "passive"))
    )
    (net (code "88") (name "Net-(D2-Pad1)") (class "Default")
      (node (ref "D2") (pin "1") (pintype "passive"))
      (node (ref "DC_IN1") (pin "1") (pintype "passive"))
    )
    (net (code "89") (name "Net-(D2-Pad2)") (class "Default")
      (node (ref "D2") (pin "2") (pintype "passive"))
      (node (ref "S2") (pin "2") (pinfunction "2_2") (pintype "passive"))
    )
    (net (code "90") (name "Net-(D3-K)") (class "Default")
      (node (ref "D3") (pin "2") (pinfunction "K_2") (pintype "passive"))
      (node (ref "IC1") (pin "3") (pinfunction "SW_3") (pintype "passive"))
      (node (ref "L2") (pin "2") (pinfunction "2_2") (pintype "passive"))
    )
    (net (code "91") (name "Net-(EARTHNET1-LED(G)_K)") (class "Default")
      (node (ref "EARTHNET1") (pin "10") (pinfunction "LED(G)_K_10") (pintype "passive"))
      (node (ref "R24") (pin "2") (pintype "passive"))
    )
    (net (code "92") (name "Net-(EARTHNET1-LED(Y)_K)") (class "Default")
      (node (ref "EARTHNET1") (pin "11") (pinfunction "LED(Y)_K_11") (pintype "passive"))
      (node (ref "R25") (pin "2") (pintype "passive"))
    )
    (net (code "93") (name "Net-(IC1-EN)") (class "Default")
      (node (ref "C40") (pin "1") (pintype "passive"))
      (node (ref "IC1") (pin "4") (pinfunction "EN_4") (pintype "passive"))
    )
    (net (code "94") (name "Net-(IC1-FB)") (class "Default")
      (node (ref "IC1") (pin "2") (pinfunction "FB_2") (pintype "passive"))
      (node (ref "R33") (pin "2") (pintype "passive"))
      (node (ref "R34") (pin "1") (pintype "passive"))
    )
    (net (code "95") (name "Net-(MIC1-GND)") (class "Default")
      (node (ref "C28") (pin "2") (pintype "passive"))
      (node (ref "C30") (pin "2") (pintype "passive"))
      (node (ref "MIC1") (pin "2") (pinfunction "GND_2") (pintype "passive"))
      (node (ref "R27") (pin "2") (pintype "passive"))
    )
    (net (code "96") (name "Net-(MIC1-VCC)") (class "Default")
      (node (ref "C27") (pin "2") (pintype "passive"))
      (node (ref "C29") (pin "2") (pintype "passive"))
      (node (ref "C38") (pin "2") (pintype "passive"))
      (node (ref "MIC1") (pin "1") (pinfunction "VCC_1") (pintype "passive"))
      (node (ref "R26") (pin "2") (pintype "passive"))
      (node (ref "R28") (pin "2") (pintype "passive"))
    )
    (net (code "97") (name "Net-(P2-Pad1)") (class "Default")
      (node (ref "P2") (pin "1") (pinfunction "1_1") (pintype "passive"))
      (node (ref "R7") (pin "2") (pintype "passive"))
    )
    (net (code "98") (name "Net-(P2-Pad2)") (class "Default")
      (node (ref "P2") (pin "2") (pinfunction "2_2") (pintype "passive"))
      (node (ref "R8") (pin "2") (pintype "passive"))
    )
    (net (code "99") (name "Net-(POWER1-A)") (class "Default")
      (node (ref "POWER1") (pin "1") (pinfunction "A_1") (pintype "passive"))
      (node (ref "R5") (pin "2") (pinfunction "2_2") (pintype "passive"))
    )
    (net (code "100") (name "Net-(Q1-B)") (class "Default")
      (node (ref "Q1") (pin "2") (pinfunction "B_2") (pintype "passive"))
      (node (ref "R31") (pin "2") (pintype "passive"))
      (node (ref "R32") (pin "2") (pintype "passive"))
    )
    (net (code "101") (name "Net-(Q2-B)") (class "Default")
      (node (ref "Q2") (pin "2") (pinfunction "B_2") (pintype "passive"))
      (node (ref "R35") (pin "2") (pintype "passive"))
      (node (ref "R36") (pin "2") (pintype "passive"))
    )
    (net (code "102") (name "Net-(Q2-C)") (class "Default")
      (node (ref "P9") (pin "2") (pinfunction "2_2") (pintype "passive"))
      (node (ref "Q2") (pin "3") (pinfunction "C_3") (pintype "passive"))
    )
    (net (code "103") (name "Net-(U1-AD0{slash}SDO)") (class "Default")
      (node (ref "R4") (pin "2") (pintype "passive"))
      (node (ref "U1") (pin "9") (pinfunction "AD0/SDO_9") (pintype "passive"))
    )
    (net (code "104") (name "Net-(U1-FSYNC)") (class "Default")
      (node (ref "R6") (pin "2") (pintype "passive"))
      (node (ref "U1") (pin "11") (pinfunction "FSYNC_11") (pintype "passive"))
    )
    (net (code "105") (name "Net-(U1-REGOUT)") (class "Default")
      (node (ref "C4") (pin "2") (pinfunction "2_2") (pintype "passive"))
      (node (ref "U1") (pin "10") (pinfunction "REGOUT_10") (pintype "passive"))
    )
    (net (code "106") (name "Net-(U2-MDIO)") (class "Default")
      (node (ref "R9") (pin "2") (pintype "passive"))
      (node (ref "U2") (pin "12") (pinfunction "MDIO_12") (pintype "passive"))
    )
    (net (code "107") (name "Net-(U2-RBIAS)") (class "Default")
      (node (ref "R18") (pin "2") (pintype "passive"))
      (node (ref "U2") (pin "24") (pinfunction "RBIAS_24") (pintype "passive"))
    )
    (net (code "108") (name "Net-(U2-VDDCR)") (class "Default")
      (node (ref "C10") (pin "2") (pintype "passive"))
      (node (ref "C11") (pin "2") (pintype "passive"))
      (node (ref "U2") (pin "6") (pinfunction "VDDCR_6") (pintype "passive"))
    )
    (net (code "109") (name "Net-(U2-XTAL1{slash}CLKIN)") (class "Default")
      (node (ref "C18") (pin "2") (pintype "passive"))
      (node (ref "R19") (pin "2") (pintype "passive"))
      (node (ref "U2") (pin "5") (pinfunction "XTAL1/CLKIN_5") (pintype "passive"))
      (node (ref "Y1") (pin "2") (pinfunction "OSC2_2") (pintype "passive"))
    )
    (net (code "110") (name "Net-(U2-XTAL2)") (class "Default")
      (node (ref "C17") (pin "2") (pintype "passive"))
      (node (ref "R19") (pin "1") (pintype "passive"))
      (node (ref "U2") (pin "4") (pinfunction "XTAL2_4") (pintype "passive"))
      (node (ref "Y1") (pin "1") (pinfunction "OSC1_1") (pintype "passive"))
    )
    (net (code "111") (name "Net-(U3-CH_PD)") (class "Default")
      (node (ref "R16") (pin "2") (pintype "passive"))
      (node (ref "U3") (pin "3") (pinfunction "CH_PD_3") (pintype "passive"))
    )
    (net (code "112") (name "Net-(U3-GPIO0)") (class "Default")
      (node (ref "P3") (pin "1") (pinfunction "1_1") (pintype "passive"))
      (node (ref "U3") (pin "18") (pinfunction "GPIO0_18") (pintype "passive"))
    )
    (net (code "113") (name "Net-(U3-GPIO15)") (class "Default")
      (node (ref "R17") (pin "1") (pintype "passive"))
      (node (ref "U3") (pin "16") (pinfunction "GPIO15_16") (pintype "passive"))
    )
    (net (code "114") (name "Net-(U4-DBVDD)") (class "Default")
      (node (ref "C25") (pin "2") (pintype "passive"))
      (node (ref "C26") (pin "2") (pintype "passive"))
      (node (ref "R21") (pin "1") (pintype "passive"))
      (node (ref "U4") (pin "13") (pinfunction "DCVDD_13") (pintype "passive"))
      (node (ref "U4") (pin "14") (pinfunction "DBVDD_14") (pintype "passive"))
    )
    (net (code "115") (name "Net-(U4-LIN)") (class "Default")
      (node (ref "C28") (pin "1") (pintype "passive"))
      (node (ref "U4") (pin "2") (pinfunction "LIN_2") (pintype "passive"))
    )
    (net (code "116") (name "Net-(U4-LIP)") (class "Default")
      (node (ref "C27") (pin "1") (pintype "passive"))
      (node (ref "U4") (pin "1") (pinfunction "LIP_1") (pintype "passive"))
    )
    (net (code "117") (name "Net-(U4-LOUT2)") (class "Default")
      (node (ref "P5") (pin "2") (pinfunction "2_2") (pintype "passive"))
      (node (ref "U4") (pin "25") (pinfunction "LOUT2_25") (pintype "passive"))
    )
    (net (code "118") (name "Net-(U4-MICBIAS)") (class "Default")
      (node (ref "C37") (pin "2") (pintype "passive"))
      (node (ref "R26") (pin "1") (pintype "passive"))
      (node (ref "U4") (pin "32") (pinfunction "MICBIAS_32") (pintype "passive"))
    )
    (net (code "119") (name "Net-(U4-MODE)") (class "Default")
      (node (ref "R29") (pin "2") (pintype "passive"))
      (node (ref "U4") (pin "18") (pinfunction "MODE_18") (pintype "passive"))
    )
    (net (code "120") (name "Net-(U4-RIN)") (class "Default")
      (node (ref "C30") (pin "1") (pintype "passive"))
      (node (ref "U4") (pin "5") (pinfunction "RIN_5") (pintype "passive"))
    )
    (net (code "121") (name "Net-(U4-RIP)") (class "Default")
      (node (ref "C29") (pin "1") (pintype "passive"))
      (node (ref "U4") (pin "4") (pinfunction "RIP_4") (pintype "passive"))
    )
    (net (code "122") (name "Net-(U4-ROUT2)") (class "Default")
      (node (ref "P5") (pin "1") (pinfunction "1_1") (pintype "passive"))
      (node (ref "U4") (pin "23") (pinfunction "ROUT2_23") (pintype "passive"))
    )
    (net (code "123") (name "Net-(U4-SPKVDD)") (class "Default")
      (node (ref "C19") (pin "1") (pintype "passive"))
      (node (ref "C21") (pin "2") (pintype "passive"))
      (node (ref "R20") (pin "1") (pintype "passive"))
      (node (ref "U4") (pin "26") (pinfunction "SPKVDD_26") (pintype "passive"))
    )
    (net (code "124") (name "Net-(U4-VMID)") (class "Default")
      (node (ref "C36") (pin "2") (pintype "passive"))
      (node (ref "U4") (pin "27") (pinfunction "VMID_27") (pintype "passive"))
    )
    (net (code "125") (name "unconnected-(EARTHNET1-NC-Pad7)") (class "Default")
      (node (ref "EARTHNET1") (pin "7") (pinfunction "NC_7") (pintype "passive+no_connect"))
    )
    (net (code "126") (name "unconnected-(J1-Pad12)") (class "Default")
      (node (ref "J1") (pin "12") (pinfunction "12_12") (pintype "passive+no_connect"))
    )
    (net (code "127") (name "unconnected-(J1-Pad13)") (class "Default")
      (node (ref "J1") (pin "13") (pinfunction "13_13") (pintype "passive+no_connect"))
    )
    (net (code "128") (name "unconnected-(J1-Pad14)") (class "Default")
      (node (ref "J1") (pin "14") (pinfunction "14_14") (pintype "passive+no_connect"))
    )
    (net (code "129") (name "unconnected-(J1-Pad15)") (class "Default")
      (node (ref "J1") (pin "15") (pinfunction "15_15") (pintype "passive+no_connect"))
    )
    (net (code "130") (name "unconnected-(J1-Pad16)") (class "Default")
      (node (ref "J1") (pin "16") (pinfunction "16_16") (pintype "passive+no_connect"))
    )
    (net (code "131") (name "unconnected-(J1-Pad17)") (class "Default")
      (node (ref "J1") (pin "17") (pinfunction "17_17") (pintype "passive+no_connect"))
    )
    (net (code "132") (name "unconnected-(J1-Pad18)") (class "Default")
      (node (ref "J1") (pin "18") (pinfunction "18_18") (pintype "passive+no_connect"))
    )
    (net (code "133") (name "unconnected-(J1-Pad19)") (class "Default")
      (node (ref "J1") (pin "19") (pinfunction "19_19") (pintype "passive+no_connect"))
    )
    (net (code "134") (name "unconnected-(J1-Pad20)") (class "Default")
      (node (ref "J1") (pin "20") (pinfunction "20_20") (pintype "passive+no_connect"))
    )
    (net (code "135") (name "unconnected-(J1-Pad21)") (class "Default")
      (node (ref "J1") (pin "21") (pinfunction "21_21") (pintype "passive+no_connect"))
    )
    (net (code "136") (name "unconnected-(J1-Pad22)") (class "Default")
      (node (ref "J1") (pin "22") (pinfunction "22_22") (pintype "passive+no_connect"))
    )
    (net (code "137") (name "unconnected-(J1-Pad23)") (class "Default")
      (node (ref "J1") (pin "23") (pinfunction "23_23") (pintype "passive+no_connect"))
    )
    (net (code "138") (name "unconnected-(J1-Pad24)") (class "Default")
      (node (ref "J1") (pin "24") (pinfunction "24_24") (pintype "passive+no_connect"))
    )
    (net (code "139") (name "unconnected-(J1-Pad25)") (class "Default")
      (node (ref "J1") (pin "25") (pinfunction "25_25") (pintype "passive+no_connect"))
    )
    (net (code "140") (name "unconnected-(J1-Pad26)") (class "Default")
      (node (ref "J1") (pin "26") (pinfunction "26_26") (pintype "passive+no_connect"))
    )
    (net (code "141") (name "unconnected-(J1-Pad27)") (class "Default")
      (node (ref "J1") (pin "27") (pinfunction "27_27") (pintype "passive+no_connect"))
    )
    (net (code "142") (name "unconnected-(J1-Pad28)") (class "Default")
      (node (ref "J1") (pin "28") (pinfunction "28_28") (pintype "passive+no_connect"))
    )
    (net (code "143") (name "unconnected-(J1-Pad29)") (class "Default")
      (node (ref "J1") (pin "29") (pinfunction "29_29") (pintype "passive+no_connect"))
    )
    (net (code "144") (name "unconnected-(J1-Pad30)") (class "Default")
      (node (ref "J1") (pin "30") (pinfunction "30_30") (pintype "passive+no_connect"))
    )
    (net (code "145") (name "unconnected-(J1-Pad36)") (class "Default")
      (node (ref "J1") (pin "36") (pinfunction "36_36") (pintype "passive+no_connect"))
    )
    (net (code "146") (name "unconnected-(J1-Pad37)") (class "Default")
      (node (ref "J1") (pin "37") (pinfunction "37_37") (pintype "passive+no_connect"))
    )
    (net (code "147") (name "unconnected-(J1-Pad38)") (class "Default")
      (node (ref "J1") (pin "38") (pinfunction "38_38") (pintype "passive+no_connect"))
    )
    (net (code "148") (name "unconnected-(J1-Pad39)") (class "Default")
      (node (ref "J1") (pin "39") (pinfunction "39_39") (pintype "passive+no_connect"))
    )
    (net (code "149") (name "unconnected-(J1-Pad40)") (class "Default")
      (node (ref "J1") (pin "40") (pinfunction "40_40") (pintype "passive+no_connect"))
    )
    (net (code "150") (name "unconnected-(J1-Pad41)") (class "Default")
      (node (ref "J1") (pin "41") (pinfunction "41_41") (pintype "passive+no_connect"))
    )
    (net (code "151") (name "unconnected-(J1-Pad42)") (class "Default")
      (node (ref "J1") (pin "42") (pinfunction "42_42") (pintype "passive+no_connect"))
    )
    (net (code "152") (name "unconnected-(J1-Pad43)") (class "Default")
      (node (ref "J1") (pin "43") (pinfunction "43_43") (pintype "passive+no_connect"))
    )
    (net (code "153") (name "unconnected-(J1-Pad44)") (class "Default")
      (node (ref "J1") (pin "44") (pinfunction "44_44") (pintype "passive+no_connect"))
    )
    (net (code "154") (name "unconnected-(J1-Pad45)") (class "Default")
      (node (ref "J1") (pin "45") (pinfunction "45_45") (pintype "passive+no_connect"))
    )
    (net (code "155") (name "unconnected-(J1-Pad46)") (class "Default")
      (node (ref "J1") (pin "46") (pinfunction "46_46") (pintype "passive+no_connect"))
    )
    (net (code "156") (name "unconnected-(J1-Pad47)") (class "Default")
      (node (ref "J1") (pin "47") (pinfunction "47_47") (pintype "passive+no_connect"))
    )
    (net (code "157") (name "unconnected-(J1-Pad48)") (class "Default")
      (node (ref "J1") (pin "48") (pinfunction "48_48") (pintype "passive+no_connect"))
    )
    (net (code "158") (name "unconnected-(J1-Pad49)") (class "Default")
      (node (ref "J1") (pin "49") (pinfunction "49_49") (pintype "passive+no_connect"))
    )
    (net (code "159") (name "unconnected-(J1-Pad50)") (class "Default")
      (node (ref "J1") (pin "50") (pinfunction "50_50") (pintype "passive+no_connect"))
    )
    (net (code "160") (name "unconnected-(J1-Pad51)") (class "Default")
      (node (ref "J1") (pin "51") (pinfunction "51_51") (pintype "passive+no_connect"))
    )
    (net (code "161") (name "unconnected-(J1-Pad52)") (class "Default")
      (node (ref "J1") (pin "52") (pinfunction "52_52") (pintype "passive+no_connect"))
    )
    (net (code "162") (name "unconnected-(J1-Pad53)") (class "Default")
      (node (ref "J1") (pin "53") (pinfunction "53_53") (pintype "passive+no_connect"))
    )
    (net (code "163") (name "unconnected-(J1-Pad54)") (class "Default")
      (node (ref "J1") (pin "54") (pinfunction "54_54") (pintype "passive+no_connect"))
    )
    (net (code "164") (name "unconnected-(P10-Pad16)") (class "Default")
      (node (ref "P10") (pin "16") (pinfunction "16_16") (pintype "passive+no_connect"))
    )
    (net (code "165") (name "unconnected-(S2-Pad1)") (class "Default")
      (node (ref "S2") (pin "1") (pinfunction "1_1") (pintype "passive+no_connect"))
    )
    (net (code "166") (name "unconnected-(S2-Pad4)") (class "Default")
      (node (ref "S2") (pin "4") (pinfunction "4_4") (pintype "passive+no_connect"))
    )
    (net (code "167") (name "unconnected-(S2-Pad5)") (class "Default")
      (node (ref "S2") (pin "5") (pinfunction "5_5") (pintype "passive+no_connect"))
    )
    (net (code "168") (name "unconnected-(S2-Pad6)") (class "Default")
      (node (ref "S2") (pin "6") (pinfunction "6_6") (pintype "passive+no_connect"))
    )
    (net (code "169") (name "unconnected-(U1-AUX-CL-Pad7)") (class "Default")
      (node (ref "U1") (pin "7") (pinfunction "AUX-CL_7") (pintype "passive+no_connect"))
    )
    (net (code "170") (name "unconnected-(U1-AUX-DA-Pad21)") (class "Default")
      (node (ref "U1") (pin "21") (pinfunction "AUX-DA_21") (pintype "passive+no_connect"))
    )
    (net (code "171") (name "unconnected-(U1-INT-Pad12)") (class "Default")
      (node (ref "U1") (pin "12") (pinfunction "INT_12") (pintype "passive+no_connect"))
    )
    (net (code "172") (name "unconnected-(U1-NC-Pad2)") (class "Default")
      (node (ref "U1") (pin "2") (pinfunction "NC_2") (pintype "passive+no_connect"))
    )
    (net (code "173") (name "unconnected-(U1-NC-Pad3)") (class "Default")
      (node (ref "U1") (pin "3") (pinfunction "NC_3") (pintype "passive+no_connect"))
    )
    (net (code "174") (name "unconnected-(U1-NC-Pad4)") (class "Default")
      (node (ref "U1") (pin "4") (pinfunction "NC_4") (pintype "passive+no_connect"))
    )
    (net (code "175") (name "unconnected-(U1-NC-Pad5)") (class "Default")
      (node (ref "U1") (pin "5") (pinfunction "NC_5") (pintype "passive+no_connect"))
    )
    (net (code "176") (name "unconnected-(U1-NC-Pad6)") (class "Default")
      (node (ref "U1") (pin "6") (pinfunction "NC_6") (pintype "passive+no_connect"))
    )
    (net (code "177") (name "unconnected-(U1-NC-Pad14)") (class "Default")
      (node (ref "U1") (pin "14") (pinfunction "NC_14") (pintype "passive+no_connect"))
    )
    (net (code "178") (name "unconnected-(U1-NC-Pad15)") (class "Default")
      (node (ref "U1") (pin "15") (pinfunction "NC_15") (pintype "passive+no_connect"))
    )
    (net (code "179") (name "unconnected-(U1-NC-Pad16)") (class "Default")
      (node (ref "U1") (pin "16") (pinfunction "NC_16") (pintype "passive+no_connect"))
    )
    (net (code "180") (name "unconnected-(U1-NC-Pad17)") (class "Default")
      (node (ref "U1") (pin "17") (pinfunction "NC_17") (pintype "passive+no_connect"))
    )
    (net (code "181") (name "unconnected-(U1-NC-Pad19)") (class "Default")
      (node (ref "U1") (pin "19") (pinfunction "NC_19") (pintype "passive+no_connect"))
    )
    (net (code "182") (name "unconnected-(U2-RXER{slash}PHYAD0-Pad10)") (class "Default")
      (node (ref "U2") (pin "10") (pinfunction "RXER/PHYAD0_10") (pintype "passive+no_connect"))
    )
    (net (code "183") (name "unconnected-(U3-ADC-Pad2)") (class "Default")
      (node (ref "U3") (pin "2") (pinfunction "ADC_2") (pintype "passive+no_connect"))
    )
    (net (code "184") (name "unconnected-(U3-CS0-Pad9)") (class "Default")
      (node (ref "U3") (pin "9") (pinfunction "CS0_9") (pintype "passive+no_connect"))
    )
    (net (code "185") (name "unconnected-(U3-GPIO02-Pad17)") (class "Default")
      (node (ref "U3") (pin "17") (pinfunction "GPIO02_17") (pintype "passive+no_connect"))
    )
    (net (code "186") (name "unconnected-(U3-GPIO04-Pad19)") (class "Default")
      (node (ref "U3") (pin "19") (pinfunction "GPIO04_19") (pintype "passive+no_connect"))
    )
    (net (code "187") (name "unconnected-(U3-GPIO05-Pad20)") (class "Default")
      (node (ref "U3") (pin "20") (pinfunction "GPIO05_20") (pintype "passive+no_connect"))
    )
    (net (code "188") (name "unconnected-(U3-GPIO9-Pad11)") (class "Default")
      (node (ref "U3") (pin "11") (pinfunction "GPIO9_11") (pintype "passive+no_connect"))
    )
    (net (code "189") (name "unconnected-(U3-GPIO10-Pad12)") (class "Default")
      (node (ref "U3") (pin "12") (pinfunction "GPIO10_12") (pintype "passive+no_connect"))
    )
    (net (code "190") (name "unconnected-(U3-GPIO12-Pad6)") (class "Default")
      (node (ref "U3") (pin "6") (pinfunction "GPIO12_6") (pintype "passive+no_connect"))
    )
    (net (code "191") (name "unconnected-(U3-GPIO13-Pad7)") (class "Default")
      (node (ref "U3") (pin "7") (pinfunction "GPIO13_7") (pintype "passive+no_connect"))
    )
    (net (code "192") (name "unconnected-(U3-GPIO14-Pad5)") (class "Default")
      (node (ref "U3") (pin "5") (pinfunction "GPIO14_5") (pintype "passive+no_connect"))
    )
    (net (code "193") (name "unconnected-(U3-GPIO16-Pad4)") (class "Default")
      (node (ref "U3") (pin "4") (pinfunction "GPIO16_4") (pintype "passive+no_connect"))
    )
    (net (code "194") (name "unconnected-(U3-MISO-Pad10)") (class "Default")
      (node (ref "U3") (pin "10") (pinfunction "MISO_10") (pintype "passive+no_connect"))
    )
    (net (code "195") (name "unconnected-(U3-MOSI-Pad13)") (class "Default")
      (node (ref "U3") (pin "13") (pinfunction "MOSI_13") (pintype "passive+no_connect"))
    )
    (net (code "196") (name "unconnected-(U3-SCLK-Pad14)") (class "Default")
      (node (ref "U3") (pin "14") (pinfunction "SCLK_14") (pintype "passive+no_connect"))
    )
    (net (code "197") (name "unconnected-(U4-AUXL-Pad19)") (class "Default")
      (node (ref "U4") (pin "19") (pinfunction "AUXL_19") (pintype "passive+no_connect"))
    )
    (net (code "198") (name "unconnected-(U4-AUXR-Pad20)") (class "Default")
      (node (ref "U4") (pin "20") (pinfunction "AUXR_20") (pintype "passive+no_connect"))
    )
    (net (code "199") (name "unconnected-(U4-CSB{slash}GPIO1-Pad15)") (class "Default")
      (node (ref "U4") (pin "15") (pinfunction "CSB/GPIO1_15") (pintype "passive+no_connect"))
    )
    (net (code "200") (name "unconnected-(U4-L2{slash}GPIO2-Pad3)") (class "Default")
      (node (ref "U4") (pin "3") (pinfunction "L2/GPIO2_3") (pintype "passive+no_connect"))
    )
    (net (code "201") (name "unconnected-(U4-OUT3-Pad22)") (class "Default")
      (node (ref "U4") (pin "22") (pinfunction "OUT3_22") (pintype "passive+no_connect"))
    )
    (net (code "202") (name "unconnected-(U4-OUT4-Pad21)") (class "Default")
      (node (ref "U4") (pin "21") (pinfunction "OUT4_21") (pintype "passive+no_connect"))
    )
    (net (code "203") (name "unconnected-(U4-R2{slash}GPIO3-Pad6)") (class "Default")
      (node (ref "U4") (pin "6") (pinfunction "R2/GPIO3_6") (pintype "passive+no_connect"))
    )
    (net (code "204") (name "unconnected-(U5-CTS-Pad23)") (class "Default")
      (node (ref "U5") (pin "23") (pinfunction "CTS_23") (pintype "passive+no_connect"))
    )
    (net (code "205") (name "unconnected-(U5-DCD-Pad1)") (class "Default")
      (node (ref "U5") (pin "1") (pinfunction "DCD_1") (pintype "passive"))
    )
    (net (code "206") (name "unconnected-(U5-DSR-Pad27)") (class "Default")
      (node (ref "U5") (pin "27") (pinfunction "DSR_27") (pintype "passive+no_connect"))
    )
    (net (code "207") (name "unconnected-(U5-DTR-Pad28)") (class "Default")
      (node (ref "U5") (pin "28") (pinfunction "DTR_28") (pintype "passive+no_connect"))
    )
    (net (code "208") (name "unconnected-(U5-GND-Pad0)") (class "Default")
      (node (ref "U5") (pin "0") (pinfunction "GND_0") (pintype "passive"))
    )
    (net (code "209") (name "unconnected-(U5-NC-Pad10)") (class "Default")
      (node (ref "U5") (pin "10") (pinfunction "NC_10") (pintype "passive+no_connect"))
    )
    (net (code "210") (name "unconnected-(U5-NC-Pad13)") (class "Default")
      (node (ref "U5") (pin "13") (pinfunction "NC_13") (pintype "passive+no_connect"))
    )
    (net (code "211") (name "unconnected-(U5-NC-Pad14)") (class "Default")
      (node (ref "U5") (pin "14") (pinfunction "NC_14") (pintype "passive+no_connect"))
    )
    (net (code "212") (name "unconnected-(U5-NC-Pad15)") (class "Default")
      (node (ref "U5") (pin "15") (pinfunction "NC_15") (pintype "passive+no_connect"))
    )
    (net (code "213") (name "unconnected-(U5-NC-Pad16)") (class "Default")
      (node (ref "U5") (pin "16") (pinfunction "NC_16") (pintype "passive+no_connect"))
    )
    (net (code "214") (name "unconnected-(U5-NC-Pad17)") (class "Default")
      (node (ref "U5") (pin "17") (pinfunction "NC_17") (pintype "passive+no_connect"))
    )
    (net (code "215") (name "unconnected-(U5-NC-Pad18)") (class "Default")
      (node (ref "U5") (pin "18") (pinfunction "NC_18") (pintype "passive+no_connect"))
    )
    (net (code "216") (name "unconnected-(U5-NC-Pad19)") (class "Default")
      (node (ref "U5") (pin "19") (pinfunction "NC_19") (pintype "passive+no_connect"))
    )
    (net (code "217") (name "unconnected-(U5-NC-Pad20)") (class "Default")
      (node (ref "U5") (pin "20") (pinfunction "NC_20") (pintype "passive+no_connect"))
    )
    (net (code "218") (name "unconnected-(U5-NC-Pad21)") (class "Default")
      (node (ref "U5") (pin "21") (pinfunction "NC_21") (pintype "passive+no_connect"))
    )
    (net (code "219") (name "unconnected-(U5-NC-Pad22)") (class "Default")
      (node (ref "U5") (pin "22") (pinfunction "NC_22") (pintype "passive+no_connect"))
    )
    (net (code "220") (name "unconnected-(U5-RI-Pad2)") (class "Default")
      (node (ref "U5") (pin "2") (pinfunction "RI_2") (pintype "passive"))
    )
    (net (code "221") (name "unconnected-(U5-RST-Pad9)") (class "Default")
      (node (ref "U5") (pin "9") (pinfunction "RST_9") (pintype "passive+no_connect"))
    )
    (net (code "222") (name "unconnected-(U5-RTS-Pad24)") (class "Default")
      (node (ref "U5") (pin "24") (pinfunction "RTS_24") (pintype "passive+no_connect"))
    )
    (net (code "223") (name "unconnected-(U5-SUSPEND-Pad12)") (class "Default")
      (node (ref "U5") (pin "12") (pinfunction "SUSPEND_12") (pintype "passive+no_connect"))
    )
    (net (code "224") (name "unconnected-(U5-VDD-Pad6)") (class "Default")
      (node (ref "U5") (pin "6") (pinfunction "VDD_6") (pintype "passive"))
    )
    (net (code "225") (name "unconnected-(U5-~SUSPEND-Pad11)") (class "Default")
      (node (ref "U5") (pin "11") (pinfunction "~SUSPEND_11") (pintype "passive+no_connect"))
    )
    (net (code "226") (name "unconnected-(USB1-NC-Pad4)") (class "Default")
      (node (ref "USB1") (pin "4") (pinfunction "NC_4") (pintype "passive+no_connect"))
    )
  )
)
